# Sheet1.net
KiCad netlist of a schematic drawn in Altium Designer
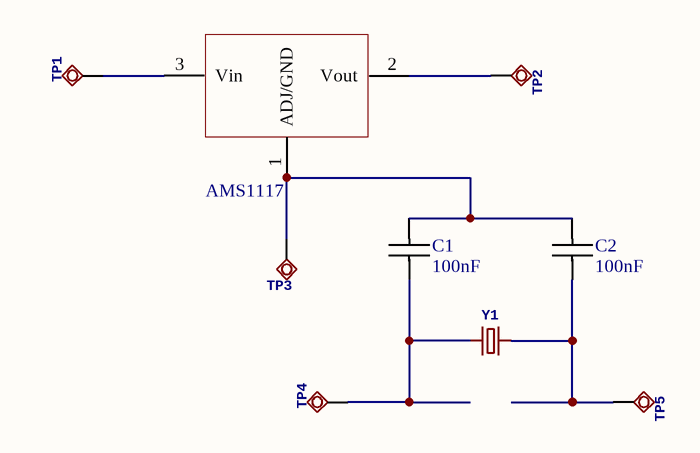
[diagram p0: Sheet1.SchDoc]

(export (version "E")
  (design (tool "Eeschema 10.0.6"))
  (components
    (comp (ref "AMS1117")
      (value "AMS1117")
      (footprint "SOT-223-3")
      (description "LDO 3.3V/5V/12V")
      (libsource (lib "IC") (part "AMS1117"))
    )
    (comp (ref "C1")
      (value "100nF")
      (footprint "C 0603 / 1608")
      (libsource (lib "Standard") (part "Capacitor"))
    )
    (comp (ref "C2")
      (value "100nF")
      (footprint "C 0603 / 1608")
      (libsource (lib "Standard") (part "Capacitor"))
    )
    (comp (ref "TP1")
      (value "Test pad")
      (footprint "TP20SQ")
      (libsource (lib "Connectors") (part "TPSQTP20SQ"))
    )
    (comp (ref "TP2")
      (value "Test pad")
      (footprint "TP20SQ")
      (libsource (lib "Connectors") (part "TPSQTP20SQ"))
    )
    (comp (ref "TP3")
      (value "Test pad")
      (footprint "TP20SQ")
      (libsource (lib "Connectors") (part "TPSQTP20SQ"))
    )
    (comp (ref "TP4")
      (value "Test pad")
      (footprint "TP20SQ")
      (libsource (lib "Connectors") (part "TPSQTP20SQ"))
    )
    (comp (ref "TP5")
      (value "Test pad")
      (footprint "TP20SQ")
      (libsource (lib "Connectors") (part "TPSQTP20SQ"))
    )
    (comp (ref "Y1")
      (value "Crystals (Generic)These are passive quartz crystals, which can be used as a clock source for a microcontroller.Crystal's are two-terminal devices. They require external \"load\" capacitors to generate an oscillating signal.")
      (footprint "HC49US")
      (fields (field (name "LIBRARYNAME") "SparkFun-Clocks"))
      (libsource (lib "SparkFun-Clocks") (part "CRYSTALPTH-HC49US"))
    )
  )
  (nets
    (net (code "1") (name "Net-(AMS1117-ADJ{slash}GND)") (class "Default")
      (node (ref "AMS1117") (pin "1") (pinfunction "ADJ/GND_1") (pintype "passive"))
      (node (ref "C1") (pin "1") (pinfunction "1_1") (pintype "passive"))
      (node (ref "C2") (pin "1") (pinfunction "1_1") (pintype "passive"))
      (node (ref "TP3") (pin "TP") (pinfunction "TP_TP") (pintype "passive"))
    )
    (net (code "2") (name "Net-(AMS1117-Vin)") (class "Default")
      (node (ref "AMS1117") (pin "3") (pinfunction "Vin_3") (pintype "passive"))
      (node (ref "TP1") (pin "TP") (pinfunction "TP_TP") (pintype "passive"))
    )
    (net (code "3") (name "Net-(AMS1117-Vout)") (class "Default")
      (node (ref "AMS1117") (pin "2") (pinfunction "Vout_2") (pintype "passive"))
      (node (ref "TP2") (pin "TP") (pinfunction "TP_TP") (pintype "passive"))
    )
    (net (code "4") (name "Net-(C1-1-Pad2)") (class "Default")
      (node (ref "C1") (pin "2") (pinfunction "1_2") (pintype "passive"))
      (node (ref "TP4") (pin "TP") (pinfunction "TP_TP") (pintype "passive"))
      (node (ref "Y1") (pin "1") (pinfunction "1_1") (pintype "passive"))
    )
    (net (code "5") (name "Net-(C2-1-Pad2)") (class "Default")
      (node (ref "C2") (pin "2") (pinfunction "1_2") (pintype "passive"))
      (node (ref "TP5") (pin "TP") (pinfunction "TP_TP") (pintype "passive"))
      (node (ref "Y1") (pin "2") (pinfunction "2_2") (pintype "passive"))
    )
  )
)
